# SCH_Auto-Sensor-Home-Light_2025-07-21.net
KiCad netlist of a schematic drawn in EasyEDA
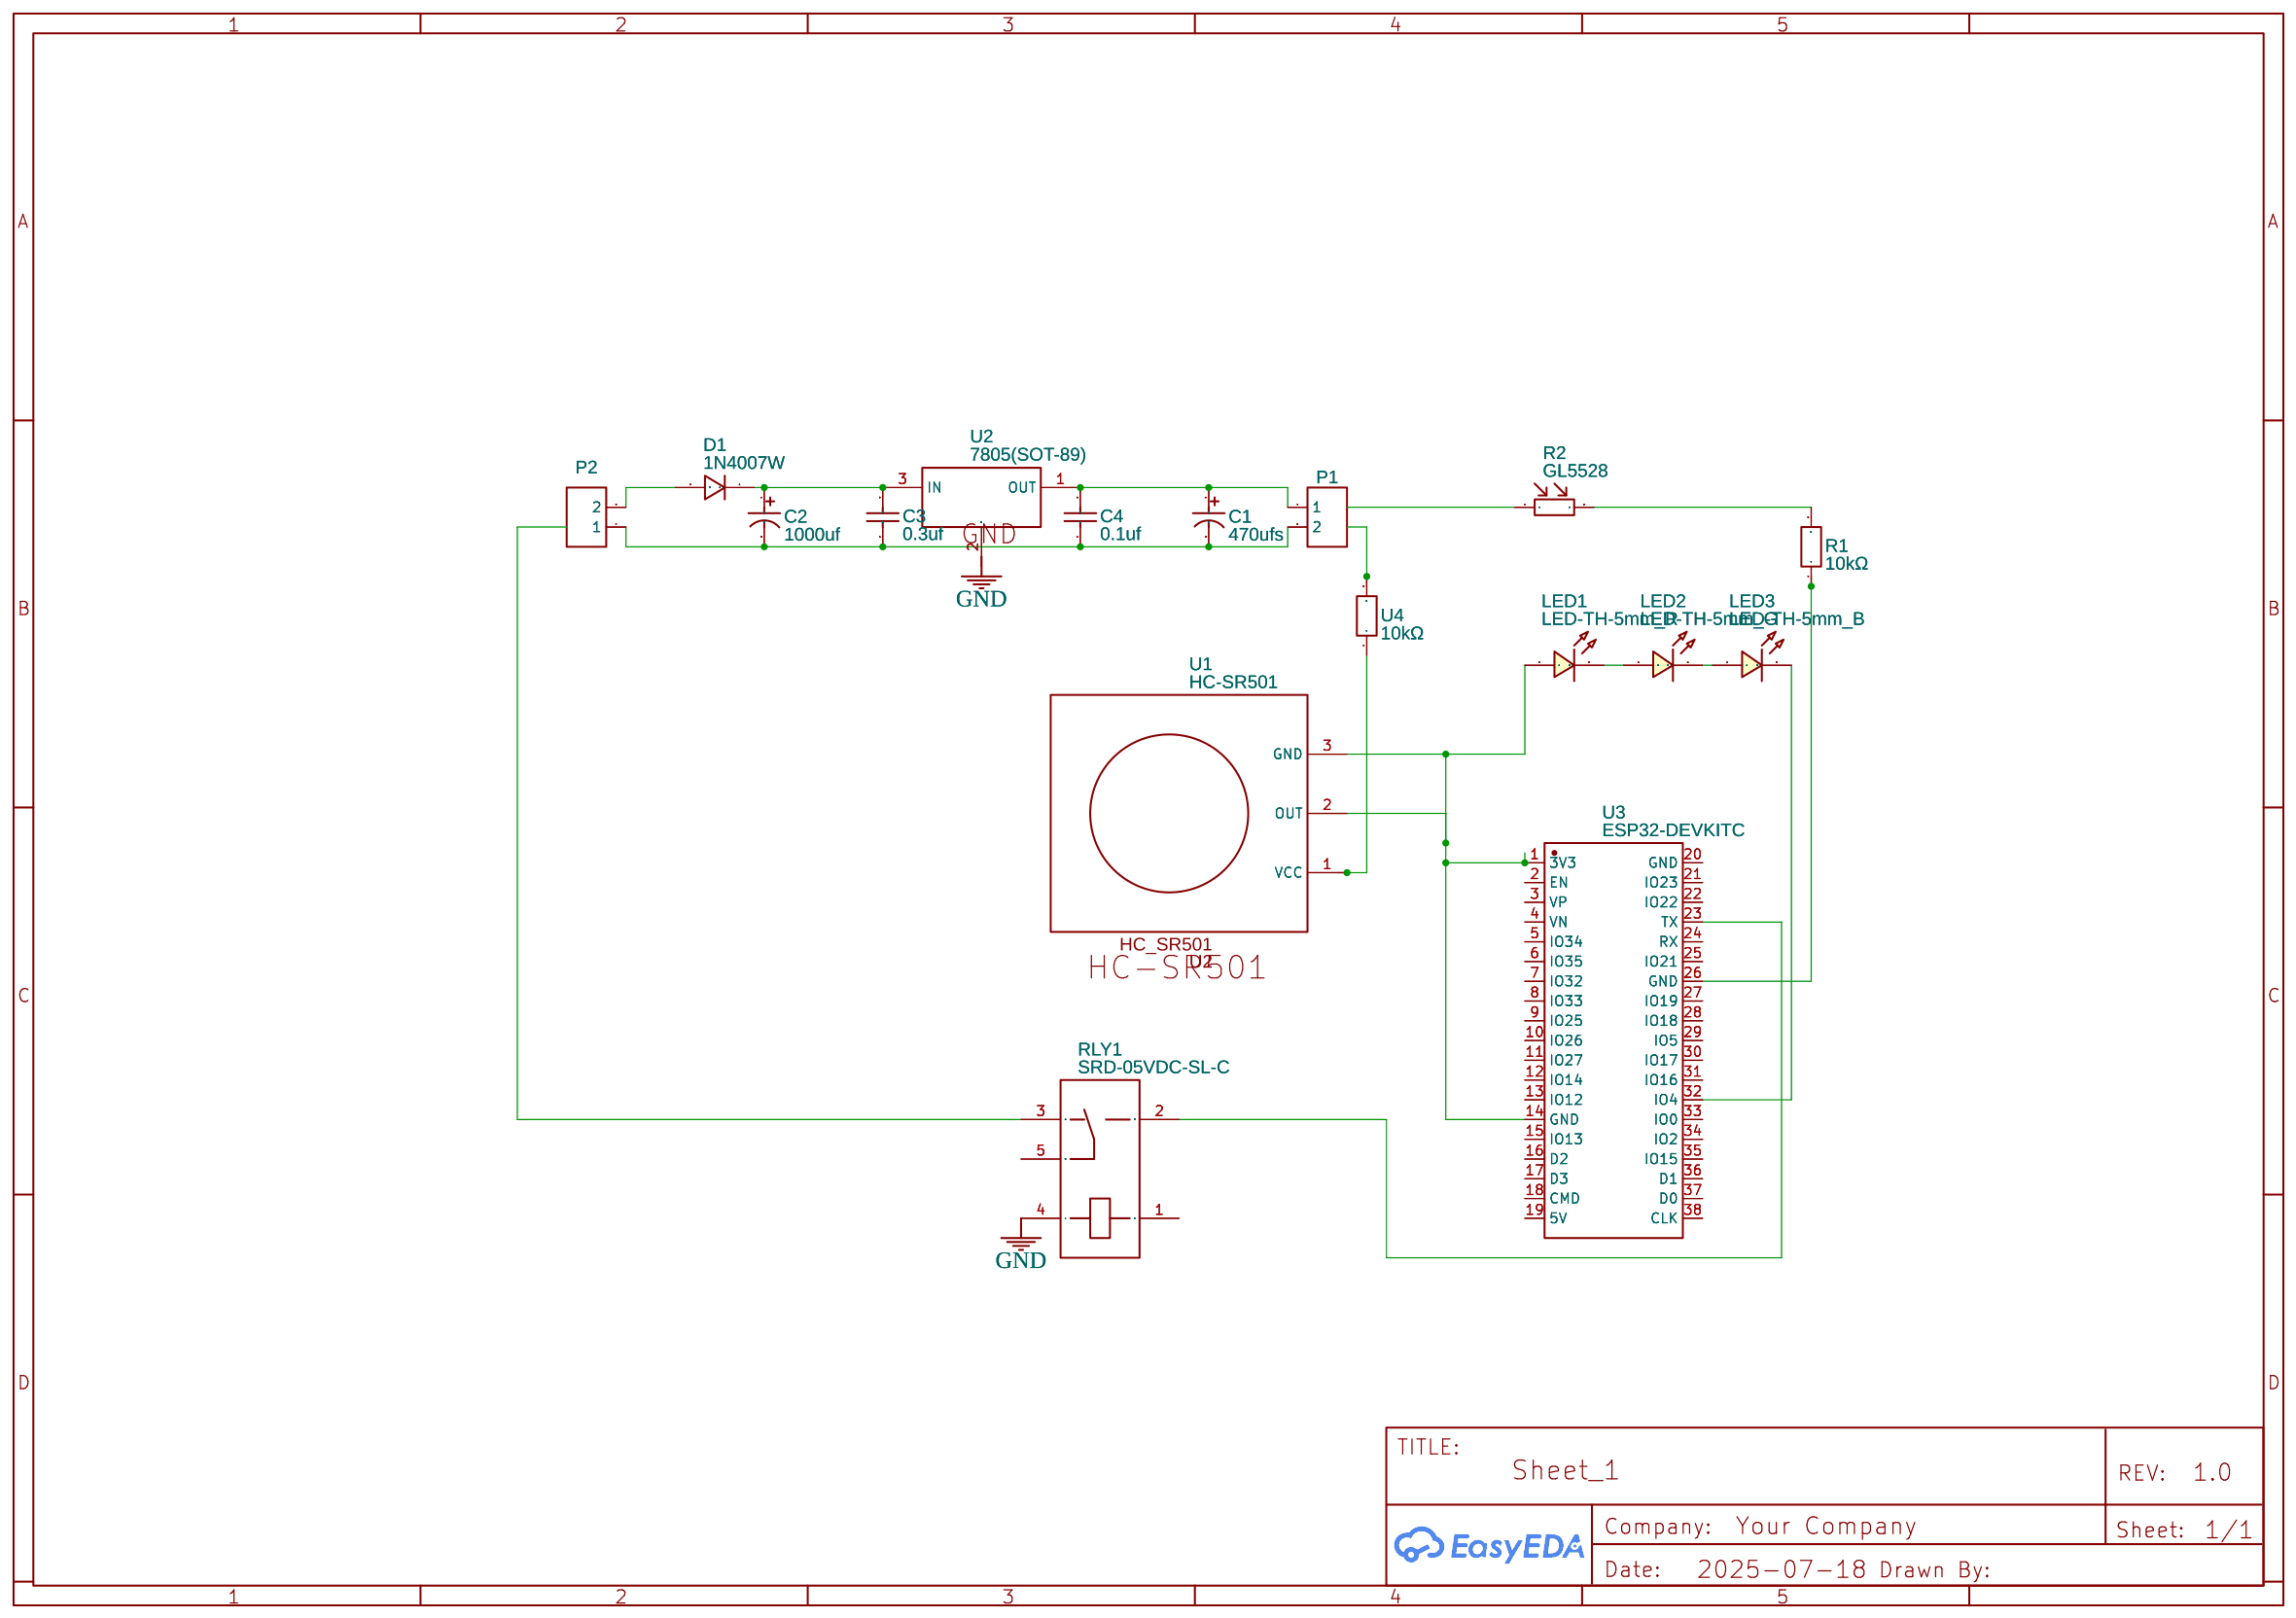
[diagram p0: schematic sheet]

(export (version "E")
  (design (tool "Eeschema 10.0.6"))
  (components
    (comp (ref "C1")
      (value "470ufs")
      (fields
        (field (name "Manufacturer Part") "KM106M016D11RR0VH2FP0")
        (field (name "Manufacturer") "CX(承兴)")
      )
      (libsource (lib "") (part "10uF 16V 5*11"))
    )
    (comp (ref "C2")
      (value "1000uf")
      (fields
        (field (name "Manufacturer Part") "KM106M016D11RR0VH2FP0")
        (field (name "Manufacturer") "CX(承兴)")
      )
      (libsource (lib "") (part "10uF 16V 5*11"))
    )
    (comp (ref "C3")
      (value "0.3uf")
      (fields
        (field (name "Manufacturer Part") "10nF(103) ±5% 100V")
        (field (name "Manufacturer") "ReliaPro")
      )
      (libsource (lib "") (part "10nF(103) ±5% 100V"))
    )
    (comp (ref "C4")
      (value "0.1uf")
      (fields
        (field (name "Manufacturer Part") "10nF(103) ±5% 100V")
        (field (name "Manufacturer") "ReliaPro")
      )
      (libsource (lib "") (part "10nF(103) ±5% 100V"))
    )
    (comp (ref "D1")
      (value "1N4007W")
      (fields (field (name "Manufacturer") "BLUE ROCKET"))
      (libsource (lib "") (part "1N4007W"))
    )
    (comp (ref "LED1")
      (value "LED-TH-5mm_R")
      (fields
        (field (name "Manufacturer Part") "333-2SURD/S530-A3")
        (field (name "Manufacturer") "EVERLIGHT(台湾亿光)")
      )
      (libsource (lib "") (part "LED-TH-5mm_R"))
    )
    (comp (ref "LED2")
      (value "LED-TH-5mm_G")
      (fields
        (field (name "Manufacturer Part") "333-2SYGD/S530-E2")
        (field (name "Manufacturer") "EVERLIGHT(台湾亿光)")
      )
      (libsource (lib "") (part "LED-TH-5mm_G"))
    )
    (comp (ref "LED3") (value "LED-TH-5mm_B") (libsource (lib "") (part "LED-TH-5mm_B")))
    (comp (ref "P1") (value "CONN-TH_2P-P5.00") (libsource (lib "") (part "CONN-TH_2P-P5.00")))
    (comp (ref "P2") (value "CONN-TH_2P-P5.00") (libsource (lib "") (part "CONN-TH_2P-P5.00_1")))
    (comp (ref "R1")
      (value "10kΩ")
      (fields (field (name "Manufacturer Part") "B5J10K") (field (name "Manufacturer") "Ohmite"))
      (libsource (lib "") (part "B5J10K"))
    )
    (comp (ref "R2")
      (value "GL5528")
      (fields (field (name "Manufacturer") "森霸"))
      (libsource (lib "") (part "GL5528"))
    )
    (comp (ref "RLY1")
      (value "SRD-05VDC-SL-C")
      (fields (field (name "Manufacturer") "松乐"))
      (libsource (lib "") (part "SRD-05VDC-SL-C"))
    )
    (comp (ref "U1")
      (value "HC-SR501")
      (fields (field (name "Manufacturer") "Generic"))
      (libsource (lib "") (part "HC-SR501"))
    )
    (comp (ref "U2")
      (value "7805(SOT-89)")
      (fields (field (name "Manufacturer Part") "CJ78L05") (field (name "Manufacturer") "CJ"))
      (libsource (lib "") (part "7805(SOT-89)"))
    )
    (comp (ref "U3")
      (value "ESP32-DEVKITC")
      (fields
        (field (name "Manufacturer Part") "ESP32-DevKitC")
        (field (name "Manufacturer") "ESPRESSIF(乐鑫)")
      )
      (libsource (lib "") (part "ESP32-DEVKITC"))
    )
    (comp (ref "U4")
      (value "10kΩ")
      (fields (field (name "Manufacturer Part") "0603 ±5% 10K") (field (name "Manufacturer") "VO(翔胜)"))
      (libsource (lib "") (part "0603 ±5% 10K"))
    )
  )
  (nets
    (net (code "1") (name "GND") (class "Default")
      (node (ref "RLY1") (pin "4") (pinfunction "4_4") (pintype "input"))
    )
    (net (code "2") (name "Net-(C1-Pad2)") (class "Default")
      (node (ref "C1") (pin "2") (pinfunction "2_2") (pintype "input"))
      (node (ref "C2") (pin "2") (pinfunction "2_2") (pintype "input"))
      (node (ref "C3") (pin "1") (pinfunction "1_1") (pintype "input"))
      (node (ref "C4") (pin "1") (pinfunction "1_1") (pintype "input"))
      (node (ref "P1") (pin "2") (pinfunction "2_2") (pintype "unspecified"))
      (node (ref "P2") (pin "1") (pinfunction "1_1") (pintype "unspecified"))
    )
    (net (code "3") (name "Net-(D1-Pad2)") (class "Default")
      (node (ref "D1") (pin "2") (pinfunction "2_2") (pintype "unspecified"))
      (node (ref "P2") (pin "2") (pinfunction "2_2") (pintype "unspecified"))
    )
    (net (code "4") (name "Net-(LED1-Pad2)") (class "Default")
      (node (ref "LED1") (pin "2") (pinfunction "2_2") (pintype "unspecified"))
      (node (ref "LED2") (pin "1") (pinfunction "1_1") (pintype "unspecified"))
    )
    (net (code "5") (name "Net-(LED2-Pad2)") (class "Default")
      (node (ref "LED2") (pin "2") (pinfunction "2_2") (pintype "unspecified"))
      (node (ref "LED3") (pin "1") (pinfunction "1_1") (pintype "unspecified"))
    )
    (net (code "6") (name "Net-(R1-Pad1)") (class "Default")
      (node (ref "R1") (pin "1") (pinfunction "1_1") (pintype "unspecified"))
      (node (ref "U3") (pin "26") (pinfunction "GND_26") (pintype "unspecified"))
    )
    (net (code "7") (name "Net-(R1-Pad2)") (class "Default")
      (node (ref "R1") (pin "2") (pinfunction "2_2") (pintype "unspecified"))
      (node (ref "R2") (pin "2") (pinfunction "2_2") (pintype "input"))
    )
    (net (code "8") (name "Net-(U1-GND)") (class "Default")
      (node (ref "LED1") (pin "1") (pinfunction "1_1") (pintype "unspecified"))
      (node (ref "U1") (pin "2") (pinfunction "OUT_2") (pintype "unspecified"))
      (node (ref "U1") (pin "3") (pinfunction "GND_3") (pintype "unspecified"))
      (node (ref "U3") (pin "1") (pinfunction "3V3_1") (pintype "unspecified"))
      (node (ref "U3") (pin "14") (pinfunction "GND_14") (pintype "unspecified"))
    )
    (net (code "9") (name "Net-(U1-VCC)") (class "Default")
      (node (ref "U1") (pin "1") (pinfunction "VCC_1") (pintype "unspecified"))
      (node (ref "U4") (pin "1") (pinfunction "1_1") (pintype "unspecified"))
    )
    (net (code "10") (name "Net-(U2-IN)") (class "Default")
      (node (ref "C2") (pin "1") (pinfunction "1_1") (pintype "input"))
      (node (ref "C3") (pin "2") (pinfunction "2_2") (pintype "input"))
      (node (ref "D1") (pin "1") (pinfunction "1_1") (pintype "unspecified"))
      (node (ref "U2") (pin "3") (pinfunction "IN_3") (pintype "passive"))
    )
    (net (code "11") (name "Net-(U2-OUT)") (class "Default")
      (node (ref "C1") (pin "1") (pinfunction "1_1") (pintype "input"))
      (node (ref "C4") (pin "2") (pinfunction "2_2") (pintype "input"))
      (node (ref "P1") (pin "1") (pinfunction "1_1") (pintype "unspecified"))
      (node (ref "U2") (pin "1") (pinfunction "OUT_1") (pintype "passive"))
    )
    (net (code "12") (name "Net-(U3-IO4)") (class "Default")
      (node (ref "LED3") (pin "2") (pinfunction "2_2") (pintype "unspecified"))
      (node (ref "U3") (pin "32") (pinfunction "IO4_32") (pintype "unspecified"))
    )
    (net (code "13") (name "Net-(U3-TX)") (class "Default")
      (node (ref "RLY1") (pin "2") (pinfunction "2_2") (pintype "input"))
      (node (ref "U3") (pin "23") (pinfunction "TX_23") (pintype "unspecified"))
    )
    (net (code "14") (name "unconnected-(R2-Pad1)") (class "Default")
      (node (ref "R2") (pin "1") (pinfunction "1_1") (pintype "input"))
    )
    (net (code "15") (name "unconnected-(RLY1-Pad1)") (class "Default")
      (node (ref "RLY1") (pin "1") (pinfunction "1_1") (pintype "input"))
    )
    (net (code "16") (name "unconnected-(RLY1-Pad3)") (class "Default")
      (node (ref "RLY1") (pin "3") (pinfunction "3_3") (pintype "input"))
    )
    (net (code "17") (name "unconnected-(RLY1-Pad5)") (class "Default")
      (node (ref "RLY1") (pin "5") (pinfunction "5_5") (pintype "input"))
    )
    (net (code "18") (name "unconnected-(U2-GND-Pad2)") (class "Default")
      (node (ref "U2") (pin "2") (pinfunction "GND_2") (pintype "passive"))
    )
    (net (code "19") (name "unconnected-(U3-5V-Pad19)") (class "Default")
      (node (ref "U3") (pin "19") (pinfunction "5V_19") (pintype "unspecified"))
    )
    (net (code "20") (name "unconnected-(U3-CLK-Pad38)") (class "Default")
      (node (ref "U3") (pin "38") (pinfunction "CLK_38") (pintype "unspecified"))
    )
    (net (code "21") (name "unconnected-(U3-CMD-Pad18)") (class "Default")
      (node (ref "U3") (pin "18") (pinfunction "CMD_18") (pintype "unspecified"))
    )
    (net (code "22") (name "unconnected-(U3-D0-Pad37)") (class "Default")
      (node (ref "U3") (pin "37") (pinfunction "D0_37") (pintype "unspecified"))
    )
    (net (code "23") (name "unconnected-(U3-D1-Pad36)") (class "Default")
      (node (ref "U3") (pin "36") (pinfunction "D1_36") (pintype "unspecified"))
    )
    (net (code "24") (name "unconnected-(U3-D2-Pad16)") (class "Default")
      (node (ref "U3") (pin "16") (pinfunction "D2_16") (pintype "unspecified"))
    )
    (net (code "25") (name "unconnected-(U3-D3-Pad17)") (class "Default")
      (node (ref "U3") (pin "17") (pinfunction "D3_17") (pintype "unspecified"))
    )
    (net (code "26") (name "unconnected-(U3-EN-Pad2)") (class "Default")
      (node (ref "U3") (pin "2") (pinfunction "EN_2") (pintype "unspecified"))
    )
    (net (code "27") (name "unconnected-(U3-GND-Pad20)") (class "Default")
      (node (ref "U3") (pin "20") (pinfunction "GND_20") (pintype "unspecified"))
    )
    (net (code "28") (name "unconnected-(U3-IO0-Pad33)") (class "Default")
      (node (ref "U3") (pin "33") (pinfunction "IO0_33") (pintype "unspecified"))
    )
    (net (code "29") (name "unconnected-(U3-IO2-Pad34)") (class "Default")
      (node (ref "U3") (pin "34") (pinfunction "IO2_34") (pintype "unspecified"))
    )
    (net (code "30") (name "unconnected-(U3-IO5-Pad29)") (class "Default")
      (node (ref "U3") (pin "29") (pinfunction "IO5_29") (pintype "unspecified"))
    )
    (net (code "31") (name "unconnected-(U3-IO12-Pad13)") (class "Default")
      (node (ref "U3") (pin "13") (pinfunction "IO12_13") (pintype "unspecified"))
    )
    (net (code "32") (name "unconnected-(U3-IO13-Pad15)") (class "Default")
      (node (ref "U3") (pin "15") (pinfunction "IO13_15") (pintype "unspecified"))
    )
    (net (code "33") (name "unconnected-(U3-IO14-Pad12)") (class "Default")
      (node (ref "U3") (pin "12") (pinfunction "IO14_12") (pintype "unspecified"))
    )
    (net (code "34") (name "unconnected-(U3-IO15-Pad35)") (class "Default")
      (node (ref "U3") (pin "35") (pinfunction "IO15_35") (pintype "unspecified"))
    )
    (net (code "35") (name "unconnected-(U3-IO16-Pad31)") (class "Default")
      (node (ref "U3") (pin "31") (pinfunction "IO16_31") (pintype "unspecified"))
    )
    (net (code "36") (name "unconnected-(U3-IO17-Pad30)") (class "Default")
      (node (ref "U3") (pin "30") (pinfunction "IO17_30") (pintype "unspecified"))
    )
    (net (code "37") (name "unconnected-(U3-IO18-Pad28)") (class "Default")
      (node (ref "U3") (pin "28") (pinfunction "IO18_28") (pintype "unspecified"))
    )
    (net (code "38") (name "unconnected-(U3-IO19-Pad27)") (class "Default")
      (node (ref "U3") (pin "27") (pinfunction "IO19_27") (pintype "unspecified"))
    )
    (net (code "39") (name "unconnected-(U3-IO21-Pad25)") (class "Default")
      (node (ref "U3") (pin "25") (pinfunction "IO21_25") (pintype "unspecified"))
    )
    (net (code "40") (name "unconnected-(U3-IO22-Pad22)") (class "Default")
      (node (ref "U3") (pin "22") (pinfunction "IO22_22") (pintype "unspecified"))
    )
    (net (code "41") (name "unconnected-(U3-IO23-Pad21)") (class "Default")
      (node (ref "U3") (pin "21") (pinfunction "IO23_21") (pintype "unspecified"))
    )
    (net (code "42") (name "unconnected-(U3-IO25-Pad9)") (class "Default")
      (node (ref "U3") (pin "9") (pinfunction "IO25_9") (pintype "unspecified"))
    )
    (net (code "43") (name "unconnected-(U3-IO26-Pad10)") (class "Default")
      (node (ref "U3") (pin "10") (pinfunction "IO26_10") (pintype "unspecified"))
    )
    (net (code "44") (name "unconnected-(U3-IO27-Pad11)") (class "Default")
      (node (ref "U3") (pin "11") (pinfunction "IO27_11") (pintype "unspecified"))
    )
    (net (code "45") (name "unconnected-(U3-IO32-Pad7)") (class "Default")
      (node (ref "U3") (pin "7") (pinfunction "IO32_7") (pintype "unspecified"))
    )
    (net (code "46") (name "unconnected-(U3-IO33-Pad8)") (class "Default")
      (node (ref "U3") (pin "8") (pinfunction "IO33_8") (pintype "unspecified"))
    )
    (net (code "47") (name "unconnected-(U3-IO34-Pad5)") (class "Default")
      (node (ref "U3") (pin "5") (pinfunction "IO34_5") (pintype "unspecified"))
    )
    (net (code "48") (name "unconnected-(U3-IO35-Pad6)") (class "Default")
      (node (ref "U3") (pin "6") (pinfunction "IO35_6") (pintype "unspecified"))
    )
    (net (code "49") (name "unconnected-(U3-RX-Pad24)") (class "Default")
      (node (ref "U3") (pin "24") (pinfunction "RX_24") (pintype "unspecified"))
    )
    (net (code "50") (name "unconnected-(U3-VN-Pad4)") (class "Default")
      (node (ref "U3") (pin "4") (pinfunction "VN_4") (pintype "unspecified"))
    )
    (net (code "51") (name "unconnected-(U3-VP-Pad3)") (class "Default")
      (node (ref "U3") (pin "3") (pinfunction "VP_3") (pintype "unspecified"))
    )
    (net (code "52") (name "unconnected-(U4-Pad2)") (class "Default")
      (node (ref "U4") (pin "2") (pinfunction "2_2") (pintype "unspecified"))
    )
  )
)
